# Cinemate.net
KiCad netlist of a schematic drawn in EAGLE
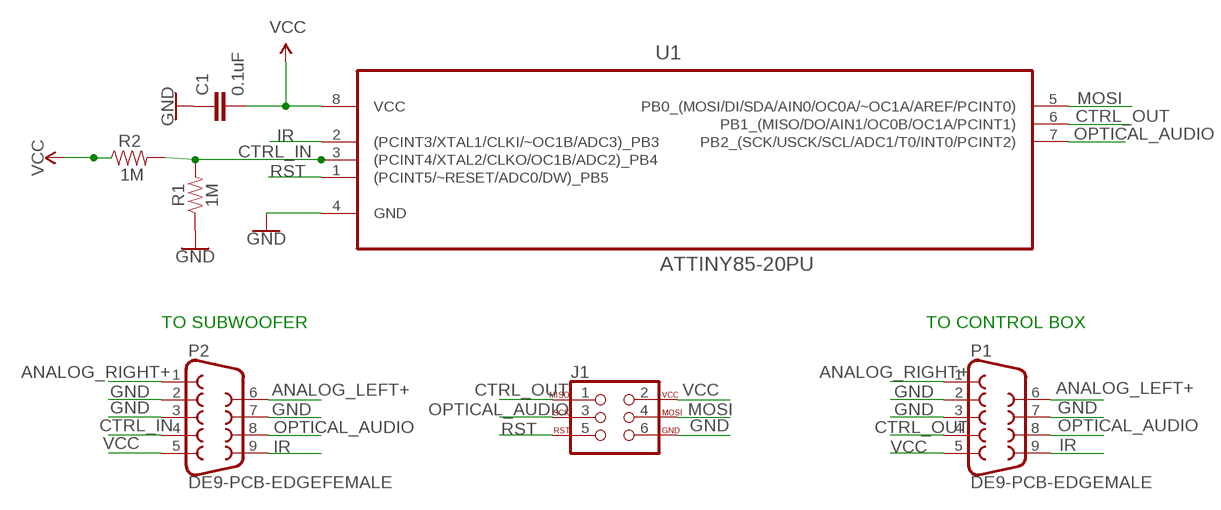
[diagram p0: schematic, sheet 1]

(export (version "E")
  (design (tool "Eeschema 10.0.6"))
  (components
    (comp (ref "C1")
      (value "0.1uF")
      (footprint "eagle-import:CAP-PTH-SMALL-KIT")
      (libsource (lib "eagle-import") (part "0.1UF-KIT-EZ-50V-20%"))
    )
    (comp (ref "J1")
      (value "AVR_SPI_PROG_3X2PTH")
      (footprint "eagle-import:2X3")
      (libsource (lib "eagle-import") (part "AVR_SPI_PROG_3X2PTH"))
    )
    (comp (ref "P1")
      (value "DE9-PCB-EDGEMALE")
      (footprint "eagle-import:DE9-EDGE-M")
      (libsource (lib "eagle-import") (part "DE9-PCB-EDGEMALE"))
    )
    (comp (ref "P2")
      (value "DE9-PCB-EDGEFEMALE")
      (footprint "eagle-import:DE9-EDGE-F")
      (libsource (lib "eagle-import") (part "DE9-PCB-EDGEFEMALE"))
    )
    (comp (ref "R1")
      (value "1M")
      (footprint "eagle-import:AXIAL-0.3")
      (libsource (lib "eagle-import") (part "RESISTORAXIAL-0.3"))
    )
    (comp (ref "R2")
      (value "1M")
      (footprint "eagle-import:AXIAL-0.3")
      (libsource (lib "eagle-import") (part "RESISTORAXIAL-0.3"))
    )
    (comp (ref "U1")
      (value "ATTINY85-20PU")
      (footprint "eagle-import:DIP254P762X533-8")
      (fields (field (name "MF") "Microchip"))
      (libsource (lib "eagle-import") (part "ATTINY85-20PU"))
    )
  )
  (nets
    (net (code "1") (name "/ANALOG_LEFT+") (class "Default")
      (node (ref "P1") (pin "6") (pinfunction "6_6") (pintype "passive"))
      (node (ref "P2") (pin "6") (pinfunction "6_6") (pintype "passive"))
    )
    (net (code "2") (name "/ANALOG_RIGHT+") (class "Default")
      (node (ref "P1") (pin "1") (pinfunction "1_1") (pintype "passive"))
      (node (ref "P2") (pin "1") (pinfunction "1_1") (pintype "passive"))
    )
    (net (code "3") (name "/CTRL_IN") (class "Default")
      (node (ref "P2") (pin "4") (pinfunction "4_4") (pintype "passive"))
      (node (ref "R1") (pin "P$2") (pinfunction "2_P$2") (pintype "passive"))
      (node (ref "R2") (pin "P$2") (pinfunction "2_P$2") (pintype "passive"))
      (node (ref "U1") (pin "3") (pinfunction "(PCINT4/XTAL2/CLKO/OC1B/ADC2)_PB4_3") (pintype "bidirectional"))
    )
    (net (code "4") (name "/CTRL_OUT") (class "Default")
      (node (ref "J1") (pin "1") (pinfunction "1_1") (pintype "passive"))
      (node (ref "P1") (pin "4") (pinfunction "4_4") (pintype "passive"))
      (node (ref "U1") (pin "6") (pinfunction "PB1_(MISO/DO/AIN1/OC0B/OC1A/PCINT1)_6") (pintype "bidirectional"))
    )
    (net (code "5") (name "/IR") (class "Default")
      (node (ref "P1") (pin "9") (pinfunction "9_9") (pintype "passive"))
      (node (ref "P2") (pin "9") (pinfunction "9_9") (pintype "passive"))
      (node (ref "U1") (pin "2") (pinfunction "(PCINT3/XTAL1/CLKI/~{OC1B/ADC3})_PB3_2") (pintype "bidirectional"))
    )
    (net (code "6") (name "/MOSI") (class "Default")
      (node (ref "J1") (pin "4") (pinfunction "4_4") (pintype "passive"))
      (node (ref "U1") (pin "5") (pinfunction "PB0_(MOSI/DI/SDA/AIN0/OC0A/~{OC1A/AREF/PCINT0})_5") (pintype "bidirectional"))
    )
    (net (code "7") (name "/OPTICAL_AUDIO") (class "Default")
      (node (ref "J1") (pin "3") (pinfunction "3_3") (pintype "passive"))
      (node (ref "P1") (pin "8") (pinfunction "8_8") (pintype "passive"))
      (node (ref "P2") (pin "8") (pinfunction "8_8") (pintype "passive"))
      (node (ref "U1") (pin "7") (pinfunction "PB2_(SCK/USCK/SCL/ADC1/T0/INT0/PCINT2)_7") (pintype "bidirectional"))
    )
    (net (code "8") (name "/RST") (class "Default")
      (node (ref "J1") (pin "5") (pinfunction "5_5") (pintype "passive"))
      (node (ref "U1") (pin "1") (pinfunction "(PCINT5/~{RESET/ADC0/DW})_PB5_1") (pintype "bidirectional"))
    )
    (net (code "9") (name "GND") (class "Default")
      (node (ref "C1") (pin "1") (pinfunction "1_1") (pintype "passive"))
      (node (ref "J1") (pin "6") (pinfunction "6_6") (pintype "passive"))
      (node (ref "P1") (pin "2") (pinfunction "2_2") (pintype "passive"))
      (node (ref "P1") (pin "3") (pinfunction "3_3") (pintype "passive"))
      (node (ref "P1") (pin "7") (pinfunction "7_7") (pintype "passive"))
      (node (ref "P2") (pin "2") (pinfunction "2_2") (pintype "passive"))
      (node (ref "P2") (pin "3") (pinfunction "3_3") (pintype "passive"))
      (node (ref "P2") (pin "7") (pinfunction "7_7") (pintype "passive"))
      (node (ref "R1") (pin "P$1") (pinfunction "1_P$1") (pintype "passive"))
      (node (ref "U1") (pin "4") (pinfunction "GND_4") (pintype "passive"))
    )
    (net (code "10") (name "VCC") (class "Default")
      (node (ref "C1") (pin "2") (pinfunction "2_2") (pintype "passive"))
      (node (ref "J1") (pin "2") (pinfunction "2_2") (pintype "passive"))
      (node (ref "P1") (pin "5") (pinfunction "5_5") (pintype "passive"))
      (node (ref "P2") (pin "5") (pinfunction "5_5") (pintype "passive"))
      (node (ref "R2") (pin "P$1") (pinfunction "1_P$1") (pintype "passive"))
      (node (ref "U1") (pin "8") (pinfunction "VCC_8") (pintype "power_in"))
    )
  )
)
